# mp3player_v6_Laderegler_LTC4063.net
KiCad netlist of a schematic drawn in EAGLE
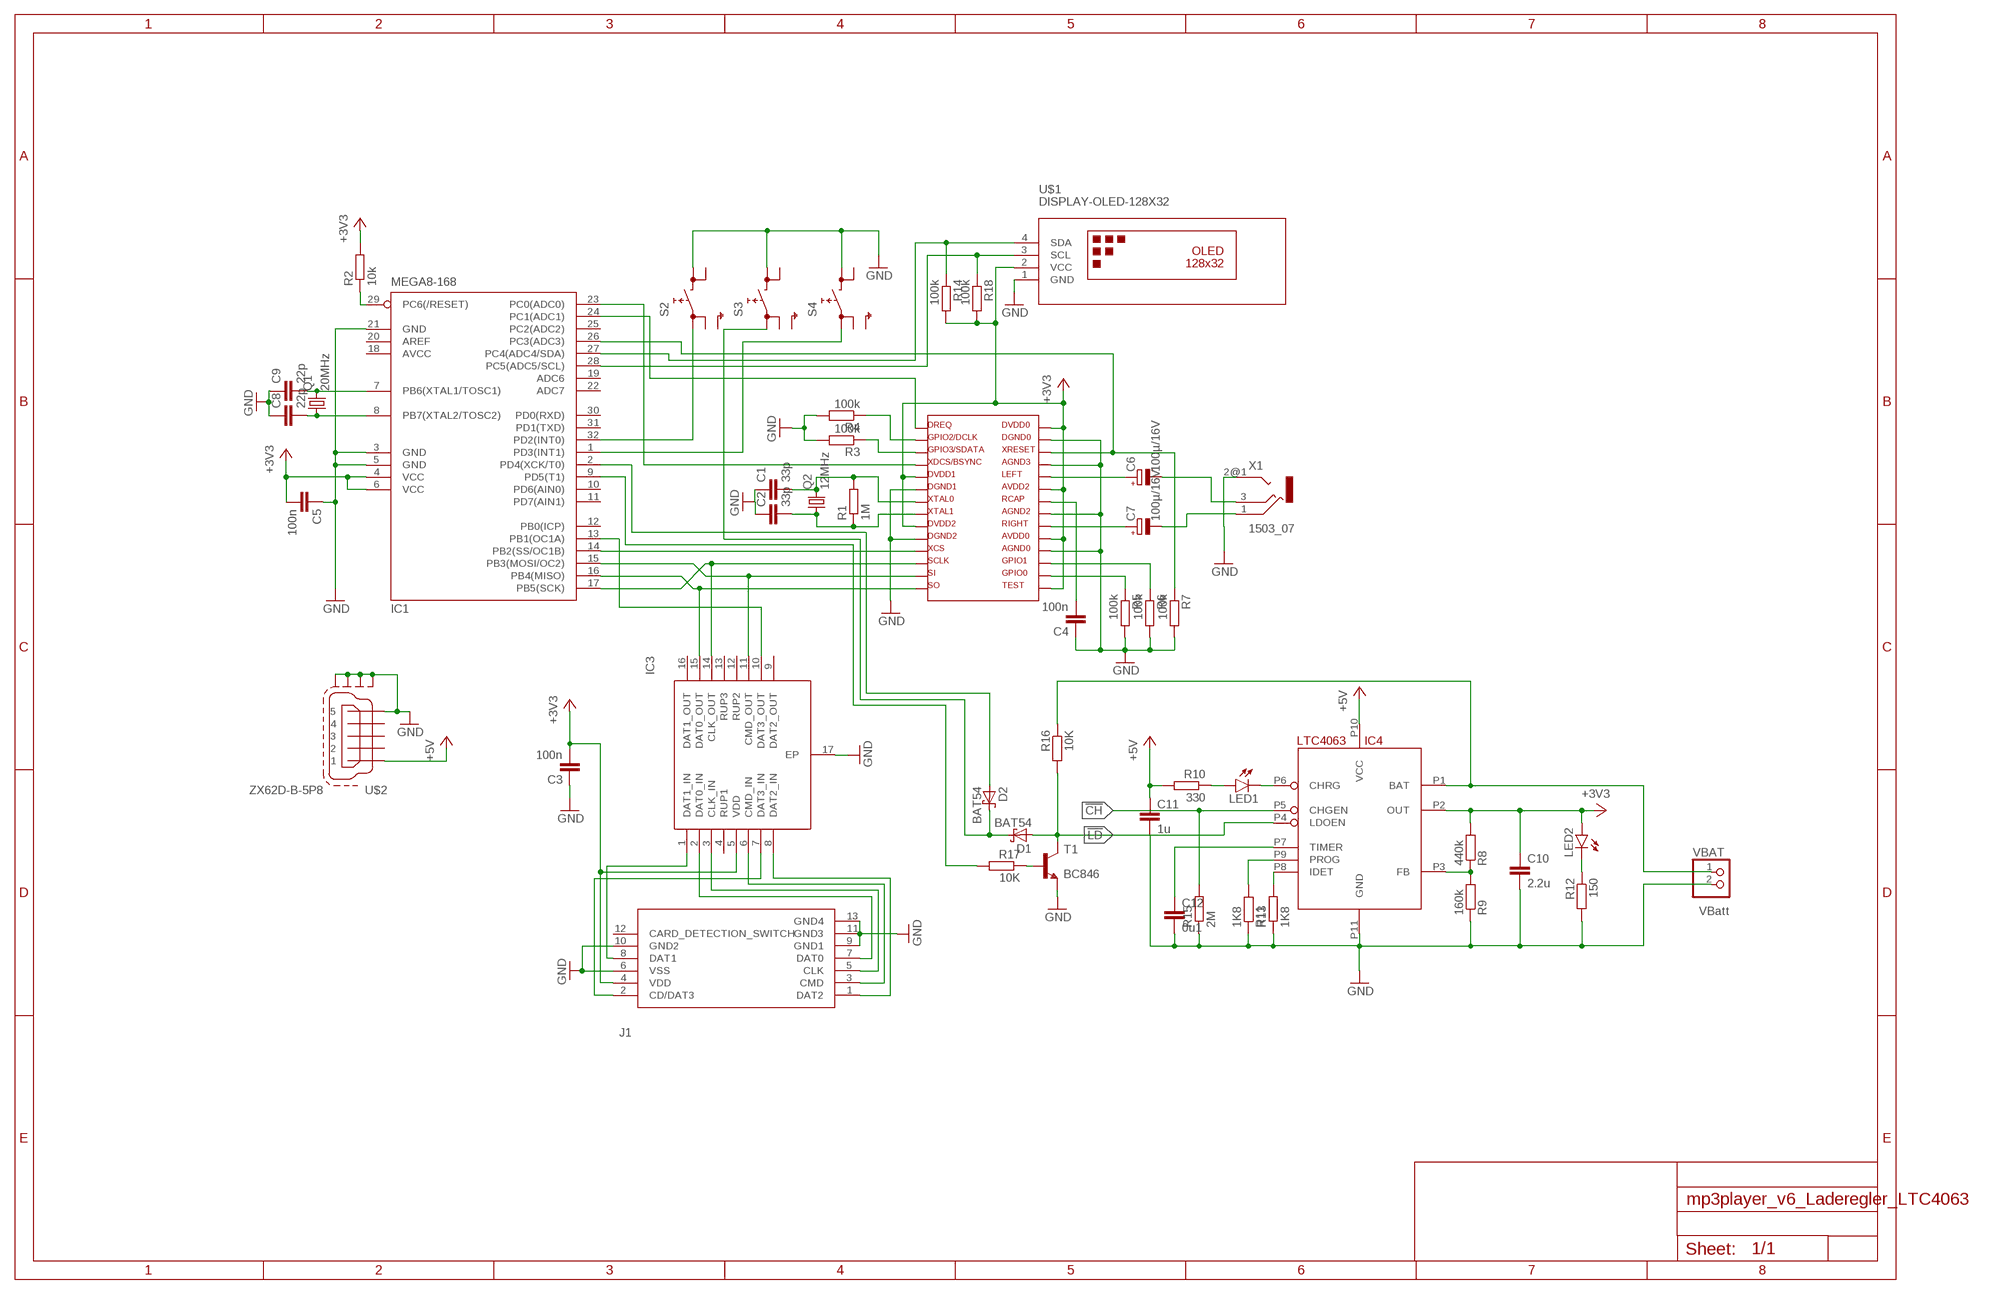
[diagram p0: schematic, sheet 1]

(export (version "E")
  (design (tool "Eeschema 10.0.6"))
  (components
    (comp (ref "C1")
      (value "33p")
      (footprint "eagle-import:C1206K")
      (libsource (lib "eagle-import") (part "C-EUC1206K"))
    )
    (comp (ref "C2")
      (value "33p")
      (footprint "eagle-import:C1206K")
      (libsource (lib "eagle-import") (part "C-EUC1206K"))
    )
    (comp (ref "C3")
      (value "100n")
      (footprint "eagle-import:C1206K")
      (libsource (lib "eagle-import") (part "C-EUC1206K"))
    )
    (comp (ref "C4")
      (value "100n")
      (footprint "eagle-import:C1206K")
      (libsource (lib "eagle-import") (part "C-EUC1206K"))
    )
    (comp (ref "C5")
      (value "100n")
      (footprint "eagle-import:C1206K")
      (libsource (lib "eagle-import") (part "C-EUC1206K"))
    )
    (comp (ref "C6")
      (value "100µ/16V")
      (footprint "eagle-import:UD-6,3X7,7_NICHICON")
      (libsource (lib "eagle-import") (part "CPOL-EUUD-6,3X7,7"))
    )
    (comp (ref "C7")
      (value "100µ/16V")
      (footprint "eagle-import:UD-6,3X7,7_NICHICON")
      (libsource (lib "eagle-import") (part "CPOL-EUUD-6,3X7,7"))
    )
    (comp (ref "C8")
      (value "22p")
      (footprint "eagle-import:C1206K")
      (libsource (lib "eagle-import") (part "rcl_334_C-EUC1206K"))
    )
    (comp (ref "C9")
      (value "22p")
      (footprint "eagle-import:C1206K")
      (libsource (lib "eagle-import") (part "rcl_334_C-EUC1206K"))
    )
    (comp (ref "C10")
      (value "2.2u")
      (footprint "eagle-import:C0805K")
      (libsource (lib "eagle-import") (part "C-EUC0805K"))
    )
    (comp (ref "C11")
      (value "1u")
      (footprint "eagle-import:C0805K")
      (libsource (lib "eagle-import") (part "C-EUC0805K"))
    )
    (comp (ref "C12")
      (value "0u1")
      (footprint "eagle-import:C0805K")
      (libsource (lib "eagle-import") (part "C-EUC0805K"))
    )
    (comp (ref "D1")
      (value "BAT54")
      (footprint "eagle-import:SOT23")
      (libsource (lib "eagle-import") (part "BAT54"))
    )
    (comp (ref "D2")
      (value "BAT54")
      (footprint "eagle-import:SOT23")
      (libsource (lib "eagle-import") (part "BAT54"))
    )
    (comp (ref "IC1")
      (value "MEGA8-168")
      (footprint "eagle-import:TQFP32-08")
      (fields (field (name "MPN") "ATMEGA8-16AU"))
      (libsource (lib "eagle-import") (part "MEGA8-AI"))
    )
    (comp (ref "IC2")
      (value "VS1011")
      (footprint "eagle-import:SOIC-28")
      (libsource (lib "eagle-import") (part "VS1011"))
    )
    (comp (ref "IC3")
      (value "ECLAMP2410P.TCT")
      (footprint "eagle-import:SON50P160X400X65-17N")
      (fields (field (name "RS_PART_NUMBER") "6910638"))
      (libsource (lib "eagle-import") (part "ECLAMP2410P.TCT"))
    )
    (comp (ref "IC4")
      (value "LTC4063")
      (footprint "eagle-import:LTC4063")
      (libsource (lib "eagle-import") (part "LTC4063"))
    )
    (comp (ref "J1")
      (value "DM3CS-SF")
      (footprint "eagle-import:DM3CS-SF")
      (fields (field (name "RS_PART_NUMBER") "1664833"))
      (libsource (lib "eagle-import") (part "DM3CS-SF"))
    )
    (comp (ref "LED1")
      (value "LG_T679-E1F1-1")
      (footprint "eagle-import:PLCC2")
      (libsource (lib "eagle-import") (part "_T679-?-1E1F1LG"))
    )
    (comp (ref "LED2")
      (value "LG_T679-E1F1-1")
      (footprint "eagle-import:PLCC2")
      (libsource (lib "eagle-import") (part "_T679-?-1E1F1LG"))
    )
    (comp (ref "Q1")
      (value "20MHz")
      (footprint "eagle-import:HC49UP")
      (libsource (lib "eagle-import") (part "crystal_204_CRYSTALHC49UP"))
    )
    (comp (ref "Q2")
      (value "12MHz")
      (footprint "eagle-import:HC49UP")
      (libsource (lib "eagle-import") (part "CRYSTALHC49UP"))
    )
    (comp (ref "R1")
      (value "1M")
      (footprint "eagle-import:R0805")
      (libsource (lib "eagle-import") (part "rcl_334_R-EU_R0805"))
    )
    (comp (ref "R2")
      (value "10k")
      (footprint "eagle-import:0207_7")
      (libsource (lib "eagle-import") (part "rcl_334_R-EU_0207/7"))
    )
    (comp (ref "R3")
      (value "100k")
      (footprint "eagle-import:R0805")
      (libsource (lib "eagle-import") (part "rcl_334_R-EU_R0805"))
    )
    (comp (ref "R4")
      (value "100k")
      (footprint "eagle-import:R0805")
      (libsource (lib "eagle-import") (part "rcl_334_R-EU_R0805"))
    )
    (comp (ref "R5")
      (value "100k")
      (footprint "eagle-import:R0805")
      (libsource (lib "eagle-import") (part "rcl_334_R-EU_R0805"))
    )
    (comp (ref "R6")
      (value "100k")
      (footprint "eagle-import:R0805")
      (libsource (lib "eagle-import") (part "rcl_334_R-EU_R0805"))
    )
    (comp (ref "R7")
      (value "100k")
      (footprint "eagle-import:0207_15")
      (libsource (lib "eagle-import") (part "rcl_334_R-EU_0207/15"))
    )
    (comp (ref "R8")
      (value "440k")
      (footprint "eagle-import:R0805")
      (libsource (lib "eagle-import") (part "rcl_334_R-EU_R0805"))
    )
    (comp (ref "R9")
      (value "160k")
      (footprint "eagle-import:R0805")
      (libsource (lib "eagle-import") (part "rcl_334_R-EU_R0805"))
    )
    (comp (ref "R10")
      (value "330")
      (footprint "eagle-import:R0805")
      (libsource (lib "eagle-import") (part "rcl_334_R-EU_R0805"))
    )
    (comp (ref "R11")
      (value "1K8")
      (footprint "eagle-import:R0805")
      (libsource (lib "eagle-import") (part "R-EU_R0805"))
    )
    (comp (ref "R12")
      (value "150")
      (footprint "eagle-import:R0805")
      (libsource (lib "eagle-import") (part "rcl_334_R-EU_R0805"))
    )
    (comp (ref "R13")
      (value "1K8")
      (footprint "eagle-import:R0805")
      (libsource (lib "eagle-import") (part "rcl_334_R-EU_R0805"))
    )
    (comp (ref "R14")
      (value "100k")
      (footprint "eagle-import:R0805")
      (libsource (lib "eagle-import") (part "rcl_334_R-EU_R0805"))
    )
    (comp (ref "R15")
      (value "2M")
      (footprint "eagle-import:R0805")
      (libsource (lib "eagle-import") (part "rcl_334_R-EU_R0805"))
    )
    (comp (ref "R16")
      (value "10K")
      (footprint "eagle-import:0207_7")
      (libsource (lib "eagle-import") (part "rcl_334_R-EU_0207/7"))
    )
    (comp (ref "R17")
      (value "10K")
      (footprint "eagle-import:R0805")
      (libsource (lib "eagle-import") (part "rcl_334_R-EU_R0805"))
    )
    (comp (ref "R18")
      (value "100k")
      (footprint "eagle-import:R0805")
      (libsource (lib "eagle-import") (part "rcl_334_R-EU_R0805"))
    )
    (comp (ref "S2")
      (value "SKHMPSE010")
      (footprint "eagle-import:SKHMPXE010")
      (libsource (lib "eagle-import") (part "SKHMPE010S"))
    )
    (comp (ref "S3")
      (value "SKHMPSE010")
      (footprint "eagle-import:SKHMPXE010")
      (libsource (lib "eagle-import") (part "SKHMPE010S"))
    )
    (comp (ref "S4")
      (value "SKHMPSE010")
      (footprint "eagle-import:SKHMPXE010")
      (libsource (lib "eagle-import") (part "SKHMPE010S"))
    )
    (comp (ref "T1")
      (value "BC846")
      (footprint "eagle-import:SOT23")
      (libsource (lib "eagle-import") (part "BC846"))
    )
    (comp (ref "U$1")
      (value "DISPLAY-OLED-128X32")
      (footprint "eagle-import:DISPLAY-OLED-128X32")
      (libsource (lib "eagle-import") (part "DISPLAY-OLED-128X32"))
    )
    (comp (ref "U$2")
      (value "ZX62D-B-5P8")
      (footprint "eagle-import:ZX62D-B-5P8")
      (libsource (lib "eagle-import") (part "ZX62D-B-5P8"))
    )
    (comp (ref "VBAT")
      (value "PINHD-1X2")
      (footprint "eagle-import:1X02")
      (libsource (lib "eagle-import") (part "PINHD-1X2"))
    )
    (comp (ref "X1")
      (value "1503_07")
      (footprint "eagle-import:1503_07")
      (libsource (lib "eagle-import") (part "1503_?07"))
    )
  )
  (nets
    (net (code "1") (name "+3V3") (class "Default")
      (node (ref "C10") (pin "1") (pinfunction "1_1") (pintype "passive"))
      (node (ref "C3") (pin "2") (pinfunction "2_2") (pintype "passive"))
      (node (ref "C5") (pin "2") (pinfunction "2_2") (pintype "passive"))
      (node (ref "IC1") (pin "4") (pinfunction "VCC_4") (pintype "power_in"))
      (node (ref "IC1") (pin "6") (pinfunction "VCC_6") (pintype "power_in"))
      (node (ref "IC2") (pin "15") (pinfunction "P$15_15") (pintype "bidirectional"))
      (node (ref "IC2") (pin "19") (pinfunction "P$19_19") (pintype "bidirectional"))
      (node (ref "IC2") (pin "23") (pinfunction "P$23_23") (pintype "bidirectional"))
      (node (ref "IC2") (pin "28") (pinfunction "P$28_28") (pintype "bidirectional"))
      (node (ref "IC2") (pin "5") (pinfunction "P$5_5") (pintype "bidirectional"))
      (node (ref "IC2") (pin "9") (pinfunction "P$9_9") (pintype "bidirectional"))
      (node (ref "IC3") (pin "5") (pinfunction "VDD_5") (pintype "bidirectional"))
      (node (ref "IC4") (pin "P2") (pinfunction "OUT_P2") (pintype "output"))
      (node (ref "J1") (pin "4") (pinfunction "VDD_4") (pintype "bidirectional"))
      (node (ref "LED2") (pin "A") (pinfunction "A_A") (pintype "passive"))
      (node (ref "R14") (pin "2") (pinfunction "2_2") (pintype "passive"))
      (node (ref "R18") (pin "2") (pinfunction "2_2") (pintype "passive"))
      (node (ref "R2") (pin "2") (pinfunction "2_2") (pintype "passive"))
      (node (ref "R8") (pin "2") (pinfunction "2_2") (pintype "passive"))
      (node (ref "U$1") (pin "2") (pinfunction "VCC_2") (pintype "power_in"))
    )
    (net (code "2") (name "+5V") (class "Default")
      (node (ref "C11") (pin "1") (pinfunction "1_1") (pintype "passive"))
      (node (ref "IC4") (pin "P10") (pinfunction "VCC_P10") (pintype "power_in"))
      (node (ref "R10") (pin "2") (pinfunction "2_2") (pintype "passive"))
      (node (ref "U$2") (pin "P$1") (pinfunction "1_P$1") (pintype "passive"))
    )
    (net (code "3") (name "/AVCC") (class "Default")
      (node (ref "IC1") (pin "18") (pinfunction "AVCC_18") (pintype "power_in"))
    )
    (net (code "4") (name "/~{CH}") (class "Default")
      (node (ref "IC4") (pin "P5") (pinfunction "CHGEN_P5") (pintype "input"))
      (node (ref "R15") (pin "2") (pinfunction "2_2") (pintype "passive"))
    )
    (net (code "5") (name "/~{LD}") (class "Default")
      (node (ref "D1") (pin "1") (pinfunction "A_1") (pintype "passive"))
      (node (ref "IC4") (pin "P4") (pinfunction "LDOEN_P4") (pintype "input"))
      (node (ref "R16") (pin "2") (pinfunction "2_2") (pintype "passive"))
      (node (ref "T1") (pin "3") (pinfunction "C_3") (pintype "passive"))
    )
    (net (code "6") (name "GND") (class "Default")
      (node (ref "C1") (pin "1") (pinfunction "1_1") (pintype "passive"))
      (node (ref "C10") (pin "2") (pinfunction "2_2") (pintype "passive"))
      (node (ref "C11") (pin "2") (pinfunction "2_2") (pintype "passive"))
      (node (ref "C12") (pin "2") (pinfunction "2_2") (pintype "passive"))
      (node (ref "C2") (pin "1") (pinfunction "1_1") (pintype "passive"))
      (node (ref "C3") (pin "1") (pinfunction "1_1") (pintype "passive"))
      (node (ref "C4") (pin "1") (pinfunction "1_1") (pintype "passive"))
      (node (ref "C5") (pin "1") (pinfunction "1_1") (pintype "passive"))
      (node (ref "C8") (pin "1") (pinfunction "1_1") (pintype "passive"))
      (node (ref "C9") (pin "1") (pinfunction "1_1") (pintype "passive"))
      (node (ref "IC1") (pin "21") (pinfunction "GND_21") (pintype "power_in"))
      (node (ref "IC1") (pin "3") (pinfunction "GND_3") (pintype "power_in"))
      (node (ref "IC1") (pin "5") (pinfunction "GND_5") (pintype "power_in"))
      (node (ref "IC2") (pin "10") (pinfunction "P$10_10") (pintype "bidirectional"))
      (node (ref "IC2") (pin "18") (pinfunction "P$18_18") (pintype "bidirectional"))
      (node (ref "IC2") (pin "21") (pinfunction "P$21_21") (pintype "bidirectional"))
      (node (ref "IC2") (pin "25") (pinfunction "P$25_25") (pintype "bidirectional"))
      (node (ref "IC2") (pin "27") (pinfunction "P$27_27") (pintype "bidirectional"))
      (node (ref "IC2") (pin "6") (pinfunction "P$6_6") (pintype "bidirectional"))
      (node (ref "IC3") (pin "17") (pinfunction "EP_17") (pintype "bidirectional"))
      (node (ref "IC4") (pin "P11") (pinfunction "GND_P11") (pintype "power_in"))
      (node (ref "J1") (pin "10") (pinfunction "GND2_10") (pintype "bidirectional"))
      (node (ref "J1") (pin "11") (pinfunction "GND3_11") (pintype "bidirectional"))
      (node (ref "J1") (pin "13") (pinfunction "GND4_13") (pintype "bidirectional"))
      (node (ref "J1") (pin "6") (pinfunction "VSS_6") (pintype "bidirectional"))
      (node (ref "J1") (pin "9") (pinfunction "GND1_9") (pintype "bidirectional"))
      (node (ref "R11") (pin "1") (pinfunction "1_1") (pintype "passive"))
      (node (ref "R12") (pin "2") (pinfunction "2_2") (pintype "passive"))
      (node (ref "R13") (pin "1") (pinfunction "1_1") (pintype "passive"))
      (node (ref "R15") (pin "1") (pinfunction "1_1") (pintype "passive"))
      (node (ref "R3") (pin "2") (pinfunction "2_2") (pintype "passive"))
      (node (ref "R4") (pin "2") (pinfunction "2_2") (pintype "passive"))
      (node (ref "R5") (pin "2") (pinfunction "2_2") (pintype "passive"))
      (node (ref "R6") (pin "2") (pinfunction "2_2") (pintype "passive"))
      (node (ref "R7") (pin "2") (pinfunction "2_2") (pintype "passive"))
      (node (ref "R9") (pin "1") (pinfunction "1_1") (pintype "passive"))
      (node (ref "S2") (pin "3") (pinfunction "2.1_3") (pintype "passive"))
      (node (ref "S3") (pin "3") (pinfunction "2.1_3") (pintype "passive"))
      (node (ref "S4") (pin "3") (pinfunction "2.1_3") (pintype "passive"))
      (node (ref "T1") (pin "2") (pinfunction "E_2") (pintype "passive"))
      (node (ref "U$1") (pin "1") (pinfunction "GND_1") (pintype "power_in"))
      (node (ref "U$2") (pin "P$5") (pinfunction "5_P$5") (pintype "passive"))
      (node (ref "U$2") (pin "SH1") (pinfunction "SH1_SH1") (pintype "passive"))
      (node (ref "U$2") (pin "SH2") (pinfunction "SH2_SH2") (pintype "passive"))
      (node (ref "U$2") (pin "SH3") (pinfunction "SH3_SH3") (pintype "passive"))
      (node (ref "U$2") (pin "SH4") (pinfunction "SH4_SH4") (pintype "passive"))
      (node (ref "VBAT") (pin "2") (pinfunction "2_2") (pintype "passive"))
      (node (ref "X1") (pin "2@1") (pinfunction "2_2@1") (pintype "passive"))
    )
    (net (code "7") (name "Net-(C6-Pad-)") (class "Default")
      (node (ref "C6") (pin "-") (pinfunction "-_-") (pintype "passive"))
      (node (ref "X1") (pin "3") (pinfunction "3_3") (pintype "passive"))
    )
    (net (code "8") (name "Net-(C7-Pad-)") (class "Default")
      (node (ref "C7") (pin "-") (pinfunction "-_-") (pintype "passive"))
      (node (ref "X1") (pin "1") (pinfunction "1_1") (pintype "passive"))
    )
    (net (code "9") (name "Net-(D1-C)") (class "Default")
      (node (ref "D1") (pin "3") (pinfunction "C_3") (pintype "passive"))
      (node (ref "D2") (pin "3") (pinfunction "C_3") (pintype "passive"))
      (node (ref "S3") (pin "1") (pinfunction "1.1_1") (pintype "passive"))
    )
    (net (code "10") (name "Net-(D2-A)") (class "Default")
      (node (ref "D2") (pin "1") (pinfunction "A_1") (pintype "passive"))
      (node (ref "IC1") (pin "2") (pinfunction "PD4(XCK/T0)_2") (pintype "bidirectional"))
    )
    (net (code "11") (name "Net-(IC1-PB1(OC1A))") (class "Default")
      (node (ref "IC1") (pin "13") (pinfunction "PB1(OC1A)_13") (pintype "bidirectional"))
      (node (ref "IC3") (pin "10") (pinfunction "DAT3_OUT_10") (pintype "bidirectional"))
    )
    (net (code "12") (name "Net-(IC1-PB2(SS{slash}OC1B))") (class "Default")
      (node (ref "IC1") (pin "14") (pinfunction "PB2(SS/OC1B)_14") (pintype "bidirectional"))
      (node (ref "IC2") (pin "11") (pinfunction "P$11_11") (pintype "bidirectional"))
    )
    (net (code "13") (name "Net-(IC1-PB3(MOSI{slash}OC2))") (class "Default")
      (node (ref "IC1") (pin "15") (pinfunction "PB3(MOSI/OC2)_15") (pintype "bidirectional"))
      (node (ref "IC2") (pin "13") (pinfunction "P$13_13") (pintype "bidirectional"))
      (node (ref "IC3") (pin "11") (pinfunction "CMD_OUT_11") (pintype "bidirectional"))
    )
    (net (code "14") (name "Net-(IC1-PB4(MISO))") (class "Default")
      (node (ref "IC1") (pin "16") (pinfunction "PB4(MISO)_16") (pintype "bidirectional"))
      (node (ref "IC2") (pin "14") (pinfunction "P$14_14") (pintype "bidirectional"))
      (node (ref "IC3") (pin "15") (pinfunction "DAT0_OUT_15") (pintype "bidirectional"))
    )
    (net (code "15") (name "Net-(IC1-PB5(SCK))") (class "Default")
      (node (ref "IC1") (pin "17") (pinfunction "PB5(SCK)_17") (pintype "bidirectional"))
      (node (ref "IC2") (pin "12") (pinfunction "P$12_12") (pintype "bidirectional"))
      (node (ref "IC3") (pin "14") (pinfunction "CLK_OUT_14") (pintype "bidirectional"))
    )
    (net (code "16") (name "Net-(IC1-PB6(XTAL1{slash}TOSC1))") (class "Default")
      (node (ref "C9") (pin "2") (pinfunction "2_2") (pintype "passive"))
      (node (ref "IC1") (pin "7") (pinfunction "PB6(XTAL1/TOSC1)_7") (pintype "bidirectional"))
      (node (ref "Q1") (pin "2") (pinfunction "2_2") (pintype "passive"))
    )
    (net (code "17") (name "Net-(IC1-PB7(XTAL2{slash}TOSC2))") (class "Default")
      (node (ref "C8") (pin "2") (pinfunction "2_2") (pintype "passive"))
      (node (ref "IC1") (pin "8") (pinfunction "PB7(XTAL2/TOSC2)_8") (pintype "bidirectional"))
      (node (ref "Q1") (pin "1") (pinfunction "1_1") (pintype "passive"))
    )
    (net (code "18") (name "Net-(IC1-PC0(ADC0))") (class "Default")
      (node (ref "IC1") (pin "23") (pinfunction "PC0(ADC0)_23") (pintype "bidirectional"))
      (node (ref "IC2") (pin "4") (pinfunction "P$4_4") (pintype "bidirectional"))
    )
    (net (code "19") (name "Net-(IC1-PC1(ADC1))") (class "Default")
      (node (ref "IC1") (pin "24") (pinfunction "PC1(ADC1)_24") (pintype "bidirectional"))
      (node (ref "IC2") (pin "1") (pinfunction "P$1_1") (pintype "bidirectional"))
    )
    (net (code "20") (name "Net-(IC1-PC3(ADC3))") (class "Default")
      (node (ref "IC1") (pin "26") (pinfunction "PC3(ADC3)_26") (pintype "bidirectional"))
      (node (ref "IC2") (pin "26") (pinfunction "P$26_26") (pintype "bidirectional"))
      (node (ref "R7") (pin "1") (pinfunction "1_1") (pintype "passive"))
    )
    (net (code "21") (name "Net-(IC1-PC4(ADC4{slash}SDA))") (class "Default")
      (node (ref "IC1") (pin "27") (pinfunction "PC4(ADC4/SDA)_27") (pintype "bidirectional"))
      (node (ref "R14") (pin "1") (pinfunction "1_1") (pintype "passive"))
      (node (ref "U$1") (pin "4") (pinfunction "SDA_4") (pintype "bidirectional"))
    )
    (net (code "22") (name "Net-(IC1-PC5(ADC5{slash}SCL))") (class "Default")
      (node (ref "IC1") (pin "28") (pinfunction "PC5(ADC5/SCL)_28") (pintype "bidirectional"))
      (node (ref "R18") (pin "1") (pinfunction "1_1") (pintype "passive"))
      (node (ref "U$1") (pin "3") (pinfunction "SCL_3") (pintype "bidirectional"))
    )
    (net (code "23") (name "Net-(IC1-PC6({slash}RESET))") (class "Default")
      (node (ref "IC1") (pin "29") (pinfunction "PC6(/RESET)_29") (pintype "bidirectional"))
      (node (ref "R2") (pin "1") (pinfunction "1_1") (pintype "passive"))
    )
    (net (code "24") (name "Net-(IC1-PD2(INT0))") (class "Default")
      (node (ref "IC1") (pin "32") (pinfunction "PD2(INT0)_32") (pintype "bidirectional"))
      (node (ref "S2") (pin "1") (pinfunction "1.1_1") (pintype "passive"))
    )
    (net (code "25") (name "Net-(IC1-PD3(INT1))") (class "Default")
      (node (ref "IC1") (pin "1") (pinfunction "PD3(INT1)_1") (pintype "bidirectional"))
      (node (ref "S4") (pin "1") (pinfunction "1.1_1") (pintype "passive"))
    )
    (net (code "26") (name "Net-(IC1-PD5(T1))") (class "Default")
      (node (ref "IC1") (pin "9") (pinfunction "PD5(T1)_9") (pintype "bidirectional"))
      (node (ref "R17") (pin "2") (pinfunction "2_2") (pintype "passive"))
    )
    (net (code "27") (name "Net-(IC2-P$2)") (class "Default")
      (node (ref "IC2") (pin "2") (pinfunction "P$2_2") (pintype "bidirectional"))
      (node (ref "R4") (pin "1") (pinfunction "1_1") (pintype "passive"))
    )
    (net (code "28") (name "Net-(IC2-P$3)") (class "Default")
      (node (ref "IC2") (pin "3") (pinfunction "P$3_3") (pintype "bidirectional"))
      (node (ref "R3") (pin "1") (pinfunction "1_1") (pintype "passive"))
    )
    (net (code "29") (name "Net-(IC2-P$7)") (class "Default")
      (node (ref "C1") (pin "2") (pinfunction "2_2") (pintype "passive"))
      (node (ref "IC2") (pin "7") (pinfunction "P$7_7") (pintype "bidirectional"))
      (node (ref "Q2") (pin "2") (pinfunction "2_2") (pintype "passive"))
      (node (ref "R1") (pin "2") (pinfunction "2_2") (pintype "passive"))
    )
    (net (code "30") (name "Net-(IC2-P$8)") (class "Default")
      (node (ref "C2") (pin "2") (pinfunction "2_2") (pintype "passive"))
      (node (ref "IC2") (pin "8") (pinfunction "P$8_8") (pintype "bidirectional"))
      (node (ref "Q2") (pin "1") (pinfunction "1_1") (pintype "passive"))
      (node (ref "R1") (pin "1") (pinfunction "1_1") (pintype "passive"))
    )
    (net (code "31") (name "Net-(IC2-P$16)") (class "Default")
      (node (ref "IC2") (pin "16") (pinfunction "P$16_16") (pintype "bidirectional"))
      (node (ref "R5") (pin "1") (pinfunction "1_1") (pintype "passive"))
    )
    (net (code "32") (name "Net-(IC2-P$17)") (class "Default")
      (node (ref "IC2") (pin "17") (pinfunction "P$17_17") (pintype "bidirectional"))
      (node (ref "R6") (pin "1") (pinfunction "1_1") (pintype "passive"))
    )
    (net (code "33") (name "Net-(IC2-P$20)") (class "Default")
      (node (ref "C7") (pin "+") (pinfunction "+_+") (pintype "passive"))
      (node (ref "IC2") (pin "20") (pinfunction "P$20_20") (pintype "bidirectional"))
    )
    (net (code "34") (name "Net-(IC2-P$22)") (class "Default")
      (node (ref "C4") (pin "2") (pinfunction "2_2") (pintype "passive"))
      (node (ref "IC2") (pin "22") (pinfunction "P$22_22") (pintype "bidirectional"))
    )
    (net (code "35") (name "Net-(IC2-P$24)") (class "Default")
      (node (ref "C6") (pin "+") (pinfunction "+_+") (pintype "passive"))
      (node (ref "IC2") (pin "24") (pinfunction "P$24_24") (pintype "bidirectional"))
    )
    (net (code "36") (name "Net-(IC3-CLK_IN)") (class "Default")
      (node (ref "IC3") (pin "3") (pinfunction "CLK_IN_3") (pintype "bidirectional"))
      (node (ref "J1") (pin "5") (pinfunction "CLK_5") (pintype "bidirectional"))
    )
    (net (code "37") (name "Net-(IC3-CMD_IN)") (class "Default")
      (node (ref "IC3") (pin "6") (pinfunction "CMD_IN_6") (pintype "bidirectional"))
      (node (ref "J1") (pin "3") (pinfunction "CMD_3") (pintype "bidirectional"))
    )
    (net (code "38") (name "Net-(IC3-DAT0_IN)") (class "Default")
      (node (ref "IC3") (pin "2") (pinfunction "DAT0_IN_2") (pintype "bidirectional"))
      (node (ref "J1") (pin "7") (pinfunction "DAT0_7") (pintype "bidirectional"))
    )
    (net (code "39") (name "Net-(IC3-DAT1_IN)") (class "Default")
      (node (ref "IC3") (pin "1") (pinfunction "DAT1_IN_1") (pintype "bidirectional"))
      (node (ref "J1") (pin "8") (pinfunction "DAT1_8") (pintype "bidirectional"))
    )
    (net (code "40") (name "Net-(IC3-DAT2_IN)") (class "Default")
      (node (ref "IC3") (pin "8") (pinfunction "DAT2_IN_8") (pintype "bidirectional"))
      (node (ref "J1") (pin "1") (pinfunction "DAT2_1") (pintype "bidirectional"))
    )
    (net (code "41") (name "Net-(IC3-DAT3_IN)") (class "Default")
      (node (ref "IC3") (pin "7") (pinfunction "DAT3_IN_7") (pintype "bidirectional"))
      (node (ref "J1") (pin "2") (pinfunction "CD/DAT3_2") (pintype "bidirectional"))
    )
    (net (code "42") (name "Net-(IC4-BAT)") (class "Default")
      (node (ref "IC4") (pin "P1") (pinfunction "BAT_P1") (pintype "output"))
      (node (ref "R16") (pin "1") (pinfunction "1_1") (pintype "passive"))
      (node (ref "VBAT") (pin "1") (pinfunction "1_1") (pintype "passive"))
    )
    (net (code "43") (name "Net-(IC4-CHRG)") (class "Default")
      (node (ref "IC4") (pin "P6") (pinfunction "CHRG_P6") (pintype "output"))
      (node (ref "LED1") (pin "C") (pinfunction "C_C") (pintype "passive"))
    )
    (net (code "44") (name "Net-(IC4-FB)") (class "Default")
      (node (ref "IC4") (pin "P3") (pinfunction "FB_P3") (pintype "passive"))
      (node (ref "R8") (pin "1") (pinfunction "1_1") (pintype "passive"))
      (node (ref "R9") (pin "2") (pinfunction "2_2") (pintype "passive"))
    )
    (net (code "45") (name "Net-(IC4-IDET)") (class "Default")
      (node (ref "IC4") (pin "P8") (pinfunction "IDET_P8") (pintype "passive"))
      (node (ref "R13") (pin "2") (pinfunction "2_2") (pintype "passive"))
    )
    (net (code "46") (name "Net-(IC4-PROG)") (class "Default")
      (node (ref "IC4") (pin "P9") (pinfunction "PROG_P9") (pintype "passive"))
      (node (ref "R11") (pin "2") (pinfunction "2_2") (pintype "passive"))
    )
    (net (code "47") (name "Net-(IC4-TIMER)") (class "Default")
      (node (ref "C12") (pin "1") (pinfunction "1_1") (pintype "passive"))
      (node (ref "IC4") (pin "P7") (pinfunction "TIMER_P7") (pintype "passive"))
    )
    (net (code "48") (name "Net-(LED1-PadA)") (class "Default")
      (node (ref "LED1") (pin "A") (pinfunction "A_A") (pintype "passive"))
      (node (ref "R10") (pin "1") (pinfunction "1_1") (pintype "passive"))
    )
    (net (code "49") (name "Net-(LED2-PadC)") (class "Default")
      (node (ref "LED2") (pin "C") (pinfunction "C_C") (pintype "passive"))
      (node (ref "R12") (pin "1") (pinfunction "1_1") (pintype "passive"))
    )
    (net (code "50") (name "Net-(T1-B)") (class "Default")
      (node (ref "R17") (pin "1") (pinfunction "1_1") (pintype "passive"))
      (node (ref "T1") (pin "1") (pinfunction "B_1") (pintype "passive"))
    )
    (net (code "51") (name "unconnected-(IC1-ADC6-Pad19)") (class "Default")
      (node (ref "IC1") (pin "19") (pinfunction "ADC6_19") (pintype "bidirectional"))
    )
    (net (code "52") (name "unconnected-(IC1-ADC7-Pad22)") (class "Default")
      (node (ref "IC1") (pin "22") (pinfunction "ADC7_22") (pintype "bidirectional"))
    )
    (net (code "53") (name "unconnected-(IC1-AREF-Pad20)") (class "Default")
      (node (ref "IC1") (pin "20") (pinfunction "AREF_20") (pintype "passive"))
    )
    (net (code "54") (name "unconnected-(IC1-PB0(ICP)-Pad12)") (class "Default")
      (node (ref "IC1") (pin "12") (pinfunction "PB0(ICP)_12") (pintype "bidirectional"))
    )
    (net (code "55") (name "unconnected-(IC1-PC2(ADC2)-Pad25)") (class "Default")
      (node (ref "IC1") (pin "25") (pinfunction "PC2(ADC2)_25") (pintype "bidirectional"))
    )
    (net (code "56") (name "unconnected-(IC1-PD0(RXD)-Pad30)") (class "Default")
      (node (ref "IC1") (pin "30") (pinfunction "PD0(RXD)_30") (pintype "bidirectional"))
    )
    (net (code "57") (name "unconnected-(IC1-PD1(TXD)-Pad31)") (class "Default")
      (node (ref "IC1") (pin "31") (pinfunction "PD1(TXD)_31") (pintype "bidirectional"))
    )
    (net (code "58") (name "unconnected-(IC1-PD6(AIN0)-Pad10)") (class "Default")
      (node (ref "IC1") (pin "10") (pinfunction "PD6(AIN0)_10") (pintype "bidirectional"))
    )
    (net (code "59") (name "unconnected-(IC1-PD7(AIN1)-Pad11)") (class "Default")
      (node (ref "IC1") (pin "11") (pinfunction "PD7(AIN1)_11") (pintype "bidirectional"))
    )
    (net (code "60") (name "unconnected-(IC3-DAT1_OUT-Pad16)") (class "Default")
      (node (ref "IC3") (pin "16") (pinfunction "DAT1_OUT_16") (pintype "bidirectional"))
    )
    (net (code "61") (name "unconnected-(IC3-DAT2_OUT-Pad9)") (class "Default")
      (node (ref "IC3") (pin "9") (pinfunction "DAT2_OUT_9") (pintype "bidirectional"))
    )
    (net (code "62") (name "unconnected-(IC3-RUP1-Pad4)") (class "Default")
      (node (ref "IC3") (pin "4") (pinfunction "RUP1_4") (pintype "bidirectional"))
    )
    (net (code "63") (name "unconnected-(IC3-RUP2-Pad12)") (class "Default")
      (node (ref "IC3") (pin "12") (pinfunction "RUP2_12") (pintype "bidirectional"))
    )
    (net (code "64") (name "unconnected-(IC3-RUP3-Pad13)") (class "Default")
      (node (ref "IC3") (pin "13") (pinfunction "RUP3_13") (pintype "bidirectional"))
    )
    (net (code "65") (name "unconnected-(J1-CARD_DETECTION_SWITCH-Pad12)") (class "Default")
      (node (ref "J1") (pin "12") (pinfunction "CARD_DETECTION_SWITCH_12") (pintype "bidirectional"))
    )
    (net (code "66") (name "unconnected-(S2-1.2-Pad2)") (class "Default")
      (node (ref "S2") (pin "2") (pinfunction "1.2_2") (pintype "passive"))
    )
    (net (code "67") (name "unconnected-(S2-2.2-Pad4)") (class "Default")
      (node (ref "S2") (pin "4") (pinfunction "2.2_4") (pintype "passive"))
    )
    (net (code "68") (name "unconnected-(S2-SH-Pad5)") (class "Default")
      (node (ref "S2") (pin "5") (pinfunction "SH_5") (pintype "passive"))
    )
    (net (code "69") (name "unconnected-(S3-1.2-Pad2)") (class "Default")
      (node (ref "S3") (pin "2") (pinfunction "1.2_2") (pintype "passive"))
    )
    (net (code "70") (name "unconnected-(S3-2.2-Pad4)") (class "Default")
      (node (ref "S3") (pin "4") (pinfunction "2.2_4") (pintype "passive"))
    )
    (net (code "71") (name "unconnected-(S3-SH-Pad5)") (class "Default")
      (node (ref "S3") (pin "5") (pinfunction "SH_5") (pintype "passive"))
    )
    (net (code "72") (name "unconnected-(S4-1.2-Pad2)") (class "Default")
      (node (ref "S4") (pin "2") (pinfunction "1.2_2") (pintype "passive"))
    )
    (net (code "73") (name "unconnected-(S4-2.2-Pad4)") (class "Default")
      (node (ref "S4") (pin "4") (pinfunction "2.2_4") (pintype "passive"))
    )
    (net (code "74") (name "unconnected-(S4-SH-Pad5)") (class "Default")
      (node (ref "S4") (pin "5") (pinfunction "SH_5") (pintype "passive"))
    )
    (net (code "75") (name "unconnected-(U$2-2-PadP$2)") (class "Default")
      (node (ref "U$2") (pin "P$2") (pinfunction "2_P$2") (pintype "passive"))
    )
    (net (code "76") (name "unconnected-(U$2-3-PadP$3)") (class "Default")
      (node (ref "U$2") (pin "P$3") (pinfunction "3_P$3") (pintype "passive"))
    )
    (net (code "77") (name "unconnected-(U$2-4-PadP$4)") (class "Default")
      (node (ref "U$2") (pin "P$4") (pinfunction "4_P$4") (pintype "passive"))
    )
    (net (code "78") (name "unconnected-(X1-2-Pad2@2)") (class "Default")
      (node (ref "X1") (pin "2@2") (pinfunction "2_2@2") (pintype "passive"))
    )
  )
)
